# bridge.net
KiCad netlist of a schematic drawn in Altium Designer
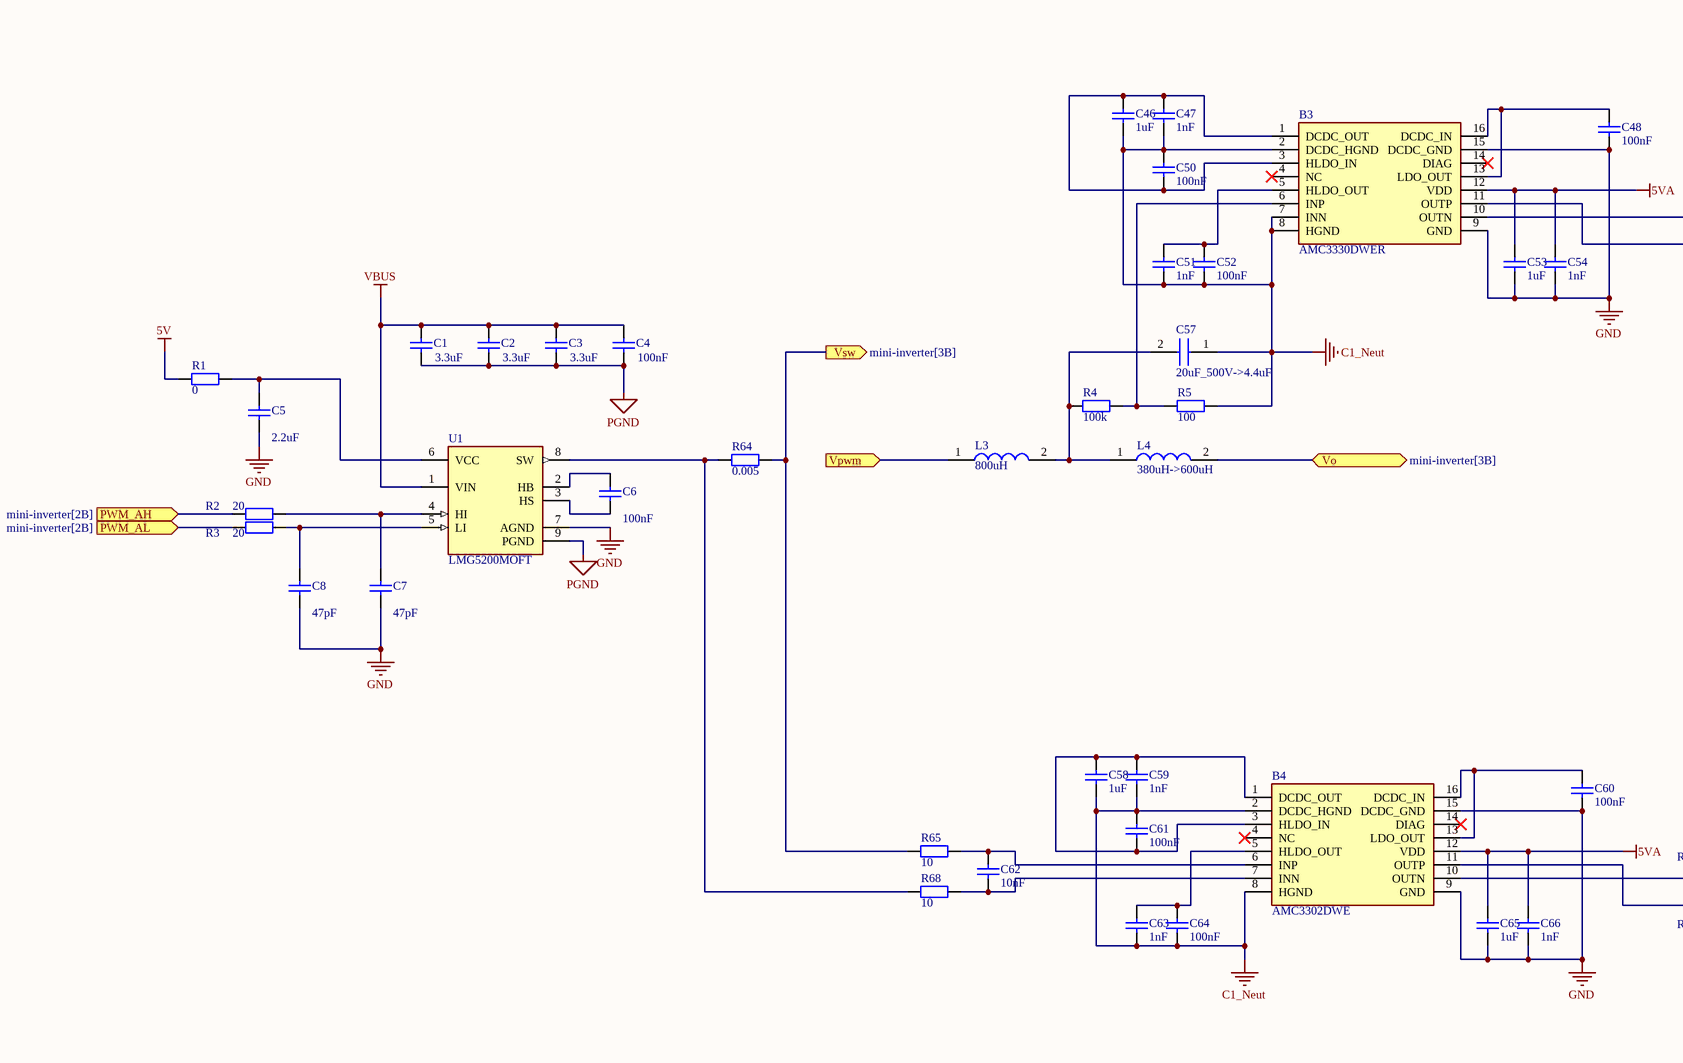
[diagram p0: bridge.SchDoc, left]
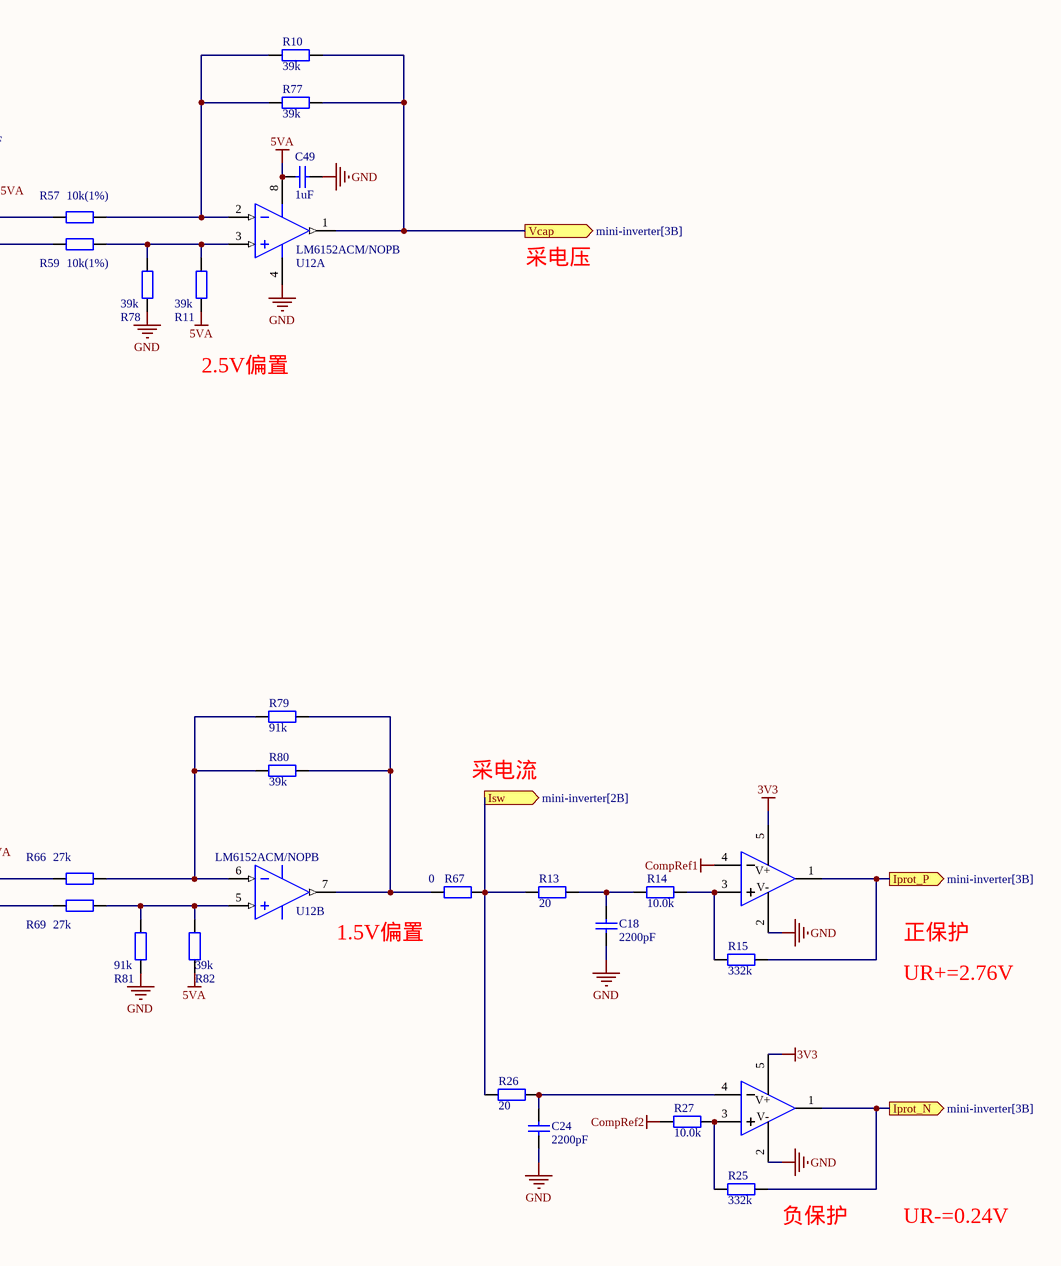
[diagram p1: bridge.SchDoc, right]

(export (version "E")
  (design (tool "Eeschema 10.0.6"))
  (components
    (comp (ref "B3")
      (value "AMC3330DWER")
      (footprint "SOIC127P1030X265-16N")
      (fields (field (name "MOUSER PART NUMBER") "595-AMC3330DWER"))
      (libsource (lib "AMC3330DWER") (part "AMC3330DWER"))
    )
    (comp (ref "B4")
      (value "AMC3302DWE")
      (footprint "SOIC127P1030X265-16N")
      (fields (field (name "MOUSER PART NUMBER") "595-AMC3302DWE"))
      (libsource (lib "AMC3302DWE") (part "AMC3302DWE"))
    )
    (comp (ref "C1")
      (value "3.3uF")
      (footprint "CAPC1608X06N")
      (description "Capacitor")
      (fields (field (name "PUBLISHER") "Altium Limited"))
      (libsource (lib "aaa2") (part "Cap"))
    )
    (comp (ref "C2")
      (value "3.3uF")
      (footprint "CAPC1608X06N")
      (description "Capacitor")
      (fields (field (name "PUBLISHER") "Altium Limited"))
      (libsource (lib "Simscale") (part "Cap"))
    )
    (comp (ref "C3")
      (value "3.3uF")
      (footprint "CAPC1608X06N")
      (description "Capacitor")
      (fields (field (name "PUBLISHER") "Altium Limited"))
      (libsource (lib "Simscale") (part "Cap"))
    )
    (comp (ref "C4")
      (value "100nF")
      (footprint "CAPC1608X06N")
      (description "Capacitor")
      (fields (field (name "PUBLISHER") "Altium Limited"))
      (libsource (lib "Simscale") (part "Cap"))
    )
    (comp (ref "C5")
      (value "2.2uF")
      (footprint "CAPC1608X06N")
      (description "Capacitor")
      (fields (field (name "PUBLISHER") "Altium Limited"))
      (libsource (lib "Simscale") (part "Cap"))
    )
    (comp (ref "C6")
      (value "100nF")
      (footprint "CAPC1608X06N")
      (description "Capacitor")
      (fields (field (name "PUBLISHER") "Altium Limited"))
      (libsource (lib "Simscale") (part "Cap"))
    )
    (comp (ref "C7")
      (value "47pF")
      (footprint "CAPC1608X06N")
      (description "Capacitor")
      (fields (field (name "PUBLISHER") "Altium Limited"))
      (libsource (lib "Simscale") (part "Cap"))
    )
    (comp (ref "C8")
      (value "47pF")
      (footprint "CAPC1608X06N")
      (description "Capacitor")
      (fields (field (name "PUBLISHER") "Altium Limited"))
      (libsource (lib "Simscale") (part "Cap"))
    )
    (comp (ref "C18")
      (value "2200pF")
      (footprint "CAPC1608X06N")
      (description "Capacitor")
      (fields (field (name "PUBLISHER") "Altium Limited"))
      (libsource (lib "Simscale") (part "Cap"))
    )
    (comp (ref "C24")
      (value "2200pF")
      (footprint "CAPC1608X06N")
      (description "Capacitor")
      (fields (field (name "PUBLISHER") "Altium Limited"))
      (libsource (lib "Simscale") (part "Cap"))
    )
    (comp (ref "C46")
      (value "1uF")
      (footprint "CAPC1608X06N")
      (description "Capacitor")
      (fields (field (name "PUBLISHER") "Altium Limited"))
      (libsource (lib "Simscale") (part "Cap"))
    )
    (comp (ref "C47")
      (value "1nF")
      (footprint "CAPC1608X06N")
      (description "Capacitor")
      (fields (field (name "PUBLISHER") "Altium Limited"))
      (libsource (lib "Simscale") (part "Cap"))
    )
    (comp (ref "C48")
      (value "100nF")
      (footprint "CAPC1608X06N")
      (description "Capacitor")
      (fields (field (name "PUBLISHER") "Altium Limited"))
      (libsource (lib "Simscale") (part "Cap"))
    )
    (comp (ref "C49")
      (value "1uF")
      (footprint "CAPC1608X06N")
      (description "Capacitor")
      (fields (field (name "PUBLISHER") "Altium Limited"))
      (libsource (lib "Miscellaneous Devices") (part "Cap"))
    )
    (comp (ref "C50")
      (value "100nF")
      (footprint "CAPC1608X06N")
      (description "Capacitor")
      (fields (field (name "PUBLISHER") "Altium Limited"))
      (libsource (lib "Simscale") (part "Cap"))
    )
    (comp (ref "C51")
      (value "1nF")
      (footprint "CAPC1608X06N")
      (description "Capacitor")
      (fields (field (name "PUBLISHER") "Altium Limited"))
      (libsource (lib "Simscale") (part "Cap"))
    )
    (comp (ref "C52")
      (value "100nF")
      (footprint "CAPC1608X06N")
      (description "Capacitor")
      (fields (field (name "PUBLISHER") "Altium Limited"))
      (libsource (lib "Simscale") (part "Cap"))
    )
    (comp (ref "C53")
      (value "1uF")
      (footprint "CAPC1608X06N")
      (description "Capacitor")
      (fields (field (name "PUBLISHER") "Altium Limited"))
      (libsource (lib "Simscale") (part "Cap"))
    )
    (comp (ref "C54")
      (value "1nF")
      (footprint "CAPC1608X06N")
      (description "Capacitor")
      (fields (field (name "PUBLISHER") "Altium Limited"))
      (libsource (lib "Simscale") (part "Cap"))
    )
    (comp (ref "C57")
      (value "20uF_500V->4.4uF")
      (footprint "Film Capacitor PHE450HF7220JR06L2")
      (description "KEMET PHE450 Metallised Polypropylene Film Capacitor, 180 V ac, 250 V dc, ±5%, 2.2μF, Through Hole")
      (fields (field (name "MANUFACTURER_PART_NUMBER") "PHE450HF7220JR06L2"))
      (libsource (lib "FYP_Components") (part "PHE450HF7220JR06L2"))
    )
    (comp (ref "C58")
      (value "1uF")
      (footprint "CAPC1608X06N")
      (description "Capacitor")
      (fields (field (name "PUBLISHER") "Altium Limited"))
      (libsource (lib "Simscale") (part "Cap"))
    )
    (comp (ref "C59")
      (value "1nF")
      (footprint "CAPC1608X06N")
      (description "Capacitor")
      (fields (field (name "PUBLISHER") "Altium Limited"))
      (libsource (lib "Simscale") (part "Cap"))
    )
    (comp (ref "C60")
      (value "100nF")
      (footprint "CAPC1608X06N")
      (description "Capacitor")
      (fields (field (name "PUBLISHER") "Altium Limited"))
      (libsource (lib "Simscale") (part "Cap"))
    )
    (comp (ref "C61")
      (value "100nF")
      (footprint "CAPC1608X06N")
      (description "Capacitor")
      (fields (field (name "PUBLISHER") "Altium Limited"))
      (libsource (lib "Simscale") (part "Cap"))
    )
    (comp (ref "C62")
      (value "10nF")
      (footprint "CAPC1608X06N")
      (description "Capacitor")
      (fields (field (name "PUBLISHER") "Altium Limited"))
      (libsource (lib "Simscale") (part "Cap"))
    )
    (comp (ref "C63")
      (value "1nF")
      (footprint "CAPC1608X06N")
      (description "Capacitor")
      (fields (field (name "PUBLISHER") "Altium Limited"))
      (libsource (lib "Simscale") (part "Cap"))
    )
    (comp (ref "C64")
      (value "100nF")
      (footprint "CAPC1608X06N")
      (description "Capacitor")
      (fields (field (name "PUBLISHER") "Altium Limited"))
      (libsource (lib "Simscale") (part "Cap"))
    )
    (comp (ref "C65")
      (value "1uF")
      (footprint "CAPC1608X06N")
      (description "Capacitor")
      (fields (field (name "PUBLISHER") "Altium Limited"))
      (libsource (lib "Simscale") (part "Cap"))
    )
    (comp (ref "C66")
      (value "1nF")
      (footprint "CAPC1608X06N")
      (description "Capacitor")
      (fields (field (name "PUBLISHER") "Altium Limited"))
      (libsource (lib "Simscale") (part "Cap"))
    )
    (comp (ref "L3")
      (value "800uH")
      (footprint "4mH Custom")
      (libsource (lib "FYP_Components") (part "4mH Custom Inductor"))
    )
    (comp (ref "L4")
      (value "380uH->600uH")
      (footprint "380uH Custom")
      (libsource (lib "FYP_Components") (part "380uH Custom Inductor"))
    )
    (comp (ref "R1")
      (value "0")
      (footprint "RESC1608X05N")
      (description "贴片电阻")
      (libsource (lib "Simscale") (part "0603 100KΩ (1003) 1%_4"))
    )
    (comp (ref "R2")
      (value "20")
      (footprint "RESC1608X05N")
      (description "贴片电阻")
      (libsource (lib "Simscale") (part "0603 100KΩ (1003) 1%_4"))
    )
    (comp (ref "R3")
      (value "20")
      (footprint "RESC1608X05N")
      (description "贴片电阻")
      (libsource (lib "Simscale") (part "0603 100KΩ (1003) 1%_4"))
    )
    (comp (ref "R4")
      (value "100k")
      (footprint "RESC1608X05N")
      (description "贴片电阻")
      (libsource (lib "") (part "0603 100KΩ (1003) 1%_4_1"))
    )
    (comp (ref "R5")
      (value "100")
      (footprint "RESC1608X05N")
      (description "贴片电阻")
      (libsource (lib "") (part "0603 100KΩ (1003) 1%_4_1"))
    )
    (comp (ref "R10")
      (value "39k")
      (footprint "RESC1608X05N")
      (description "Resistor")
      (fields (field (name "PUBLISHER") "Altium Limited"))
      (libsource (lib "") (part "Res2_1"))
    )
    (comp (ref "R11")
      (value "39k")
      (footprint "RESC1608X05N")
      (description "Resistor")
      (fields (field (name "PUBLISHER") "Altium Limited"))
      (libsource (lib "Miscellaneous Devices") (part "Res2"))
    )
    (comp (ref "R13")
      (value "20")
      (footprint "RESC1608X05N")
      (description "贴片电阻")
      (libsource (lib "Simscale") (part "0603 100KΩ (1003) 1%_4"))
    )
    (comp (ref "R14")
      (value "10.0k")
      (footprint "RESC1608X05N")
      (description "贴片电阻")
      (libsource (lib "Simscale") (part "0603 100KΩ (1003) 1%_4"))
    )
    (comp (ref "R15")
      (value "332k")
      (footprint "RESC1608X05N")
      (description "贴片电阻")
      (libsource (lib "Simscale") (part "0603 100KΩ (1003) 1%_4"))
    )
    (comp (ref "R25")
      (value "332k")
      (footprint "RESC1608X05N")
      (description "贴片电阻")
      (libsource (lib "Simscale") (part "0603 100KΩ (1003) 1%_4"))
    )
    (comp (ref "R26")
      (value "20")
      (footprint "RESC1608X05N")
      (description "贴片电阻")
      (libsource (lib "Simscale") (part "0603 100KΩ (1003) 1%_4"))
    )
    (comp (ref "R27")
      (value "10.0k")
      (footprint "RESC1608X05N")
      (description "贴片电阻")
      (libsource (lib "Simscale") (part "0603 100KΩ (1003) 1%_4"))
    )
    (comp (ref "R57")
      (value "10k(1%)")
      (footprint "RESC1608X05N")
      (description "Resistor")
      (fields (field (name "PUBLISHER") "Altium Limited"))
      (libsource (lib "") (part "Res2_1"))
    )
    (comp (ref "R59")
      (value "10k(1%)")
      (footprint "RESC1608X05N")
      (description "Resistor")
      (fields (field (name "PUBLISHER") "Altium Limited"))
      (libsource (lib "") (part "Res2_2"))
    )
    (comp (ref "R64")
      (value "0.005")
      (footprint "RESC1608X05N")
      (description "贴片电阻")
      (libsource (lib "") (part "0603 100KΩ (1003) 1%_4_1"))
    )
    (comp (ref "R65")
      (value "10")
      (footprint "RESC1608X05N")
      (description "贴片电阻")
      (libsource (lib "") (part "0603 100KΩ (1003) 1%_4_1"))
    )
    (comp (ref "R66")
      (value "27k")
      (footprint "RESC1608X05N")
      (description "Resistor")
      (fields (field (name "PUBLISHER") "Altium Limited"))
      (libsource (lib "") (part "Res2_1"))
    )
    (comp (ref "R67")
      (value "0")
      (footprint "RESC1608X05N")
      (description "Resistor")
      (fields (field (name "PUBLISHER") "Altium Limited"))
      (libsource (lib "") (part "Res2_1"))
    )
    (comp (ref "R68")
      (value "10")
      (footprint "RESC1608X05N")
      (description "贴片电阻")
      (libsource (lib "") (part "0603 100KΩ (1003) 1%_4_1"))
    )
    (comp (ref "R69")
      (value "27k")
      (footprint "RESC1608X05N")
      (description "Resistor")
      (fields (field (name "PUBLISHER") "Altium Limited"))
      (libsource (lib "") (part "Res2_2"))
    )
    (comp (ref "R77")
      (value "39k")
      (footprint "RESC1608X05N")
      (description "Resistor")
      (fields (field (name "PUBLISHER") "Altium Limited"))
      (libsource (lib "") (part "Res2_1"))
    )
    (comp (ref "R78")
      (value "39k")
      (footprint "RESC1608X05N")
      (description "Resistor")
      (fields (field (name "PUBLISHER") "Altium Limited"))
      (libsource (lib "Miscellaneous Devices") (part "Res2"))
    )
    (comp (ref "R79")
      (value "91k")
      (footprint "RESC1608X05N")
      (description "Resistor")
      (fields (field (name "PUBLISHER") "Altium Limited"))
      (libsource (lib "") (part "Res2_2"))
    )
    (comp (ref "R80")
      (value "39k")
      (footprint "RESC1608X05N")
      (description "Resistor")
      (fields (field (name "PUBLISHER") "Altium Limited"))
      (libsource (lib "") (part "Res2_1"))
    )
    (comp (ref "R81")
      (value "91k")
      (footprint "RESC1608X05N")
      (description "Resistor")
      (fields (field (name "PUBLISHER") "Altium Limited"))
      (libsource (lib "Miscellaneous Devices") (part "Res2"))
    )
    (comp (ref "R82")
      (value "39k")
      (footprint "RESC1608X05N")
      (description "Resistor")
      (fields (field (name "PUBLISHER") "Altium Limited"))
      (libsource (lib "Miscellaneous Devices") (part "Res2"))
    )
    (comp (ref "U1")
      (value "LMG5200MOFT")
      (footprint "FP-MOF0009A-MFG")
      (description "None")
      (libsource (lib "Altium Content Vault") (part "e04ca9006c06531c2d1851f29eb7844"))
    )
    (comp (ref "U5")
      (value "TLV3201AIDBVR")
      (footprint "SOT-23-5_L3.0-W1.7-P0.95-LS2.8-BR")
      (fields (field (name "MANUFACTURER") "TI(德州仪器)"))
      (libsource (lib "TLV3201AIDBVR1_TLV3201AIDBVR.schdoc") (part "TLV3201AIDBVR"))
    )
    (comp (ref "U7")
      (value "TLV3201AIDBVR")
      (footprint "SOT-23-5_L3.0-W1.7-P0.95-LS2.8-BR")
      (fields (field (name "MANUFACTURER") "TI(德州仪器)"))
      (libsource (lib "TLV3201AIDBVR1_TLV3201AIDBVR.schdoc") (part "TLV3201AIDBVR"))
    )
    (comp (ref "U12")
      (value "LM6152ACM/NOPB")
      (footprint "D0008A_L")
      (description "Dual and Quad 75 MHz GBW Rail-to-Rail I/O Operational Amplifiers, 8-pin Narrow SOIC, Pb-Free")
      (fields (field (name "MANUFACTURER") "Texas Instruments"))
      (libsource (lib "Simscale") (part "LM6152ACM/NOPB"))
    )
  )
  (nets
    (net (code "1") (name "/Iprot_N") (class "Default")
      (node (ref "R25") (pin "1") (pinfunction "1_1") (pintype "passive"))
      (node (ref "U7") (pin "1") (pinfunction "OUT_1") (pintype "passive"))
    )
    (net (code "2") (name "/Iprot_P") (class "Default")
      (node (ref "R15") (pin "1") (pinfunction "1_1") (pintype "passive"))
      (node (ref "U5") (pin "1") (pinfunction "OUT_1") (pintype "passive"))
    )
    (net (code "3") (name "/Isw") (class "Default")
      (node (ref "R13") (pin "2") (pinfunction "2_2") (pintype "passive"))
      (node (ref "R26") (pin "2") (pinfunction "2_2") (pintype "passive"))
      (node (ref "R67") (pin "1") (pinfunction "1_1") (pintype "passive"))
    )
    (net (code "4") (name "/PWM_AH") (class "Default")
      (node (ref "R2") (pin "2") (pinfunction "2_2") (pintype "passive"))
    )
    (net (code "5") (name "/PWM_AL") (class "Default")
      (node (ref "R3") (pin "2") (pinfunction "2_2") (pintype "passive"))
    )
    (net (code "6") (name "/Vcap") (class "Default")
      (node (ref "R10") (pin "1") (pinfunction "1_1") (pintype "passive"))
      (node (ref "R77") (pin "1") (pinfunction "1_1") (pintype "passive"))
      (node (ref "U12") (pin "1") (pinfunction "OUTA_1") (pintype "output"))
    )
    (net (code "7") (name "/Vo") (class "Default")
      (node (ref "L4") (pin "2") (pinfunction "2_2") (pintype "passive"))
    )
    (net (code "8") (name "/Vpwm") (class "Default")
      (node (ref "L3") (pin "1") (pinfunction "1_1") (pintype "passive"))
    )
    (net (code "9") (name "/Vsw") (class "Default")
      (node (ref "R64") (pin "2") (pinfunction "2_2") (pintype "passive"))
      (node (ref "R65") (pin "1") (pinfunction "1_1") (pintype "passive"))
    )
    (net (code "10") (name "3V3") (class "Default")
      (node (ref "U5") (pin "5") (pinfunction "VCC_5") (pintype "passive"))
      (node (ref "U7") (pin "5") (pinfunction "VCC_5") (pintype "passive"))
    )
    (net (code "11") (name "5V") (class "Default")
      (node (ref "R1") (pin "2") (pinfunction "2_2") (pintype "passive"))
    )
    (net (code "12") (name "5VA") (class "Default")
      (node (ref "B3") (pin "12") (pinfunction "VDD_12") (pintype "passive"))
      (node (ref "B4") (pin "12") (pinfunction "VDD_12") (pintype "passive"))
      (node (ref "C49") (pin "2") (pinfunction "2_2") (pintype "passive"))
      (node (ref "C53") (pin "1") (pinfunction "1_1") (pintype "passive"))
      (node (ref "C54") (pin "1") (pinfunction "1_1") (pintype "passive"))
      (node (ref "C65") (pin "1") (pinfunction "1_1") (pintype "passive"))
      (node (ref "C66") (pin "1") (pinfunction "1_1") (pintype "passive"))
      (node (ref "R11") (pin "1") (pinfunction "1_1") (pintype "passive"))
      (node (ref "R82") (pin "1") (pinfunction "1_1") (pintype "passive"))
      (node (ref "U12") (pin "8") (pinfunction "V+_8") (pintype "power_in"))
    )
    (net (code "13") (name "C1_Neut") (class "Default")
      (node (ref "B3") (pin "2") (pinfunction "DCDC_HGND_2") (pintype "passive"))
      (node (ref "B3") (pin "7") (pinfunction "INN_7") (pintype "passive"))
      (node (ref "B3") (pin "8") (pinfunction "HGND_8") (pintype "passive"))
      (node (ref "B4") (pin "2") (pinfunction "DCDC_HGND_2") (pintype "passive"))
      (node (ref "B4") (pin "8") (pinfunction "HGND_8") (pintype "passive"))
      (node (ref "C46") (pin "2") (pinfunction "2_2") (pintype "passive"))
      (node (ref "C47") (pin "2") (pinfunction "2_2") (pintype "passive"))
      (node (ref "C50") (pin "1") (pinfunction "1_1") (pintype "passive"))
      (node (ref "C51") (pin "2") (pinfunction "2_2") (pintype "passive"))
      (node (ref "C52") (pin "2") (pinfunction "2_2") (pintype "passive"))
      (node (ref "C57") (pin "1") (pinfunction "1_1") (pintype "passive"))
      (node (ref "C58") (pin "2") (pinfunction "2_2") (pintype "passive"))
      (node (ref "C59") (pin "2") (pinfunction "2_2") (pintype "passive"))
      (node (ref "C61") (pin "1") (pinfunction "1_1") (pintype "passive"))
      (node (ref "C63") (pin "2") (pinfunction "2_2") (pintype "passive"))
      (node (ref "C64") (pin "2") (pinfunction "2_2") (pintype "passive"))
      (node (ref "R5") (pin "2") (pinfunction "2_2") (pintype "passive"))
    )
    (net (code "14") (name "CompRef1") (class "Default")
      (node (ref "U5") (pin "4") (pinfunction "IN-_4") (pintype "passive"))
    )
    (net (code "15") (name "CompRef2") (class "Default")
      (node (ref "R27") (pin "2") (pinfunction "2_2") (pintype "passive"))
    )
    (net (code "16") (name "GND") (class "Default")
      (node (ref "B3") (pin "15") (pinfunction "DCDC_GND_15") (pintype "passive"))
      (node (ref "B3") (pin "9") (pinfunction "GND_9") (pintype "passive"))
      (node (ref "B4") (pin "15") (pinfunction "DCDC_GND_15") (pintype "passive"))
      (node (ref "B4") (pin "9") (pinfunction "GND_9") (pintype "passive"))
      (node (ref "C18") (pin "2") (pinfunction "2_2") (pintype "passive"))
      (node (ref "C24") (pin "2") (pinfunction "2_2") (pintype "passive"))
      (node (ref "C48") (pin "2") (pinfunction "2_2") (pintype "passive"))
      (node (ref "C49") (pin "1") (pinfunction "1_1") (pintype "passive"))
      (node (ref "C5") (pin "1") (pinfunction "1_1") (pintype "passive"))
      (node (ref "C53") (pin "2") (pinfunction "2_2") (pintype "passive"))
      (node (ref "C54") (pin "2") (pinfunction "2_2") (pintype "passive"))
      (node (ref "C60") (pin "2") (pinfunction "2_2") (pintype "passive"))
      (node (ref "C65") (pin "2") (pinfunction "2_2") (pintype "passive"))
      (node (ref "C66") (pin "2") (pinfunction "2_2") (pintype "passive"))
      (node (ref "C7") (pin "2") (pinfunction "2_2") (pintype "passive"))
      (node (ref "C8") (pin "2") (pinfunction "2_2") (pintype "passive"))
      (node (ref "R78") (pin "1") (pinfunction "1_1") (pintype "passive"))
      (node (ref "R81") (pin "1") (pinfunction "1_1") (pintype "passive"))
      (node (ref "U1") (pin "7") (pinfunction "AGND_7") (pintype "power_in"))
      (node (ref "U12") (pin "4") (pinfunction "V-_4") (pintype "power_in"))
      (node (ref "U5") (pin "2") (pinfunction "GND_2") (pintype "passive"))
      (node (ref "U7") (pin "2") (pinfunction "GND_2") (pintype "passive"))
    )
    (net (code "17") (name "Net-(B3-DCDC_IN)") (class "Default")
      (node (ref "B3") (pin "13") (pinfunction "LDO_OUT_13") (pintype "passive"))
      (node (ref "B3") (pin "16") (pinfunction "DCDC_IN_16") (pintype "passive"))
      (node (ref "C48") (pin "1") (pinfunction "1_1") (pintype "passive"))
    )
    (net (code "18") (name "Net-(B3-DCDC_OUT)") (class "Default")
      (node (ref "B3") (pin "1") (pinfunction "DCDC_OUT_1") (pintype "passive"))
      (node (ref "B3") (pin "3") (pinfunction "HLDO_IN_3") (pintype "passive"))
      (node (ref "C46") (pin "1") (pinfunction "1_1") (pintype "passive"))
      (node (ref "C47") (pin "1") (pinfunction "1_1") (pintype "passive"))
      (node (ref "C50") (pin "2") (pinfunction "2_2") (pintype "passive"))
    )
    (net (code "19") (name "Net-(B3-HLDO_OUT)") (class "Default")
      (node (ref "B3") (pin "5") (pinfunction "HLDO_OUT_5") (pintype "passive"))
      (node (ref "C51") (pin "1") (pinfunction "1_1") (pintype "passive"))
      (node (ref "C52") (pin "1") (pinfunction "1_1") (pintype "passive"))
    )
    (net (code "20") (name "Net-(B3-INP)") (class "Default")
      (node (ref "B3") (pin "6") (pinfunction "INP_6") (pintype "passive"))
      (node (ref "R4") (pin "2") (pinfunction "2_2") (pintype "passive"))
      (node (ref "R5") (pin "1") (pinfunction "1_1") (pintype "passive"))
    )
    (net (code "21") (name "Net-(B3-OUTN)") (class "Default")
      (node (ref "B3") (pin "10") (pinfunction "OUTN_10") (pintype "passive"))
      (node (ref "R57") (pin "2") (pinfunction "2_2") (pintype "passive"))
    )
    (net (code "22") (name "Net-(B3-OUTP)") (class "Default")
      (node (ref "B3") (pin "11") (pinfunction "OUTP_11") (pintype "passive"))
      (node (ref "R59") (pin "1") (pinfunction "1_1") (pintype "passive"))
    )
    (net (code "23") (name "Net-(B4-DCDC_IN)") (class "Default")
      (node (ref "B4") (pin "13") (pinfunction "LDO_OUT_13") (pintype "passive"))
      (node (ref "B4") (pin "16") (pinfunction "DCDC_IN_16") (pintype "passive"))
      (node (ref "C60") (pin "1") (pinfunction "1_1") (pintype "passive"))
    )
    (net (code "24") (name "Net-(B4-DCDC_OUT)") (class "Default")
      (node (ref "B4") (pin "1") (pinfunction "DCDC_OUT_1") (pintype "passive"))
      (node (ref "B4") (pin "3") (pinfunction "HLDO_IN_3") (pintype "passive"))
      (node (ref "C58") (pin "1") (pinfunction "1_1") (pintype "passive"))
      (node (ref "C59") (pin "1") (pinfunction "1_1") (pintype "passive"))
      (node (ref "C61") (pin "2") (pinfunction "2_2") (pintype "passive"))
    )
    (net (code "25") (name "Net-(B4-HLDO_OUT)") (class "Default")
      (node (ref "B4") (pin "5") (pinfunction "HLDO_OUT_5") (pintype "passive"))
      (node (ref "C63") (pin "1") (pinfunction "1_1") (pintype "passive"))
      (node (ref "C64") (pin "1") (pinfunction "1_1") (pintype "passive"))
    )
    (net (code "26") (name "Net-(B4-INN)") (class "Default")
      (node (ref "B4") (pin "7") (pinfunction "INN_7") (pintype "passive"))
      (node (ref "C62") (pin "2") (pinfunction "2_2") (pintype "passive"))
      (node (ref "R68") (pin "2") (pinfunction "2_2") (pintype "passive"))
    )
    (net (code "27") (name "Net-(B4-INP)") (class "Default")
      (node (ref "B4") (pin "6") (pinfunction "INP_6") (pintype "passive"))
      (node (ref "C62") (pin "1") (pinfunction "1_1") (pintype "passive"))
      (node (ref "R65") (pin "2") (pinfunction "2_2") (pintype "passive"))
    )
    (net (code "28") (name "Net-(B4-OUTN)") (class "Default")
      (node (ref "B4") (pin "10") (pinfunction "OUTN_10") (pintype "passive"))
      (node (ref "R66") (pin "2") (pinfunction "2_2") (pintype "passive"))
    )
    (net (code "29") (name "Net-(B4-OUTP)") (class "Default")
      (node (ref "B4") (pin "11") (pinfunction "OUTP_11") (pintype "passive"))
      (node (ref "R69") (pin "1") (pinfunction "1_1") (pintype "passive"))
    )
    (net (code "30") (name "Net-(C18-Pad1)") (class "Default")
      (node (ref "C18") (pin "1") (pinfunction "1_1") (pintype "passive"))
      (node (ref "R13") (pin "1") (pinfunction "1_1") (pintype "passive"))
      (node (ref "R14") (pin "2") (pinfunction "2_2") (pintype "passive"))
    )
    (net (code "31") (name "Net-(C57-Pad2)") (class "Default")
      (node (ref "C57") (pin "2") (pinfunction "2_2") (pintype "passive"))
      (node (ref "L3") (pin "2") (pinfunction "2_2") (pintype "passive"))
      (node (ref "L4") (pin "1") (pinfunction "1_1") (pintype "passive"))
      (node (ref "R4") (pin "1") (pinfunction "1_1") (pintype "passive"))
    )
    (net (code "32") (name "Net-(U1-HB)") (class "Default")
      (node (ref "C6") (pin "1") (pinfunction "1_1") (pintype "passive"))
      (node (ref "U1") (pin "2") (pinfunction "HB_2") (pintype "passive"))
    )
    (net (code "33") (name "Net-(U1-HI)") (class "Default")
      (node (ref "C7") (pin "1") (pinfunction "1_1") (pintype "passive"))
      (node (ref "R2") (pin "1") (pinfunction "1_1") (pintype "passive"))
      (node (ref "U1") (pin "4") (pinfunction "HI_4") (pintype "input"))
    )
    (net (code "34") (name "Net-(U1-HS)") (class "Default")
      (node (ref "C6") (pin "2") (pinfunction "2_2") (pintype "passive"))
      (node (ref "U1") (pin "3") (pinfunction "HS_3") (pintype "passive"))
    )
    (net (code "35") (name "Net-(U1-LI)") (class "Default")
      (node (ref "C8") (pin "1") (pinfunction "1_1") (pintype "passive"))
      (node (ref "R3") (pin "1") (pinfunction "1_1") (pintype "passive"))
      (node (ref "U1") (pin "5") (pinfunction "LI_5") (pintype "input"))
    )
    (net (code "36") (name "Net-(U1-SW)") (class "Default")
      (node (ref "R64") (pin "1") (pinfunction "1_1") (pintype "passive"))
      (node (ref "R68") (pin "1") (pinfunction "1_1") (pintype "passive"))
      (node (ref "U1") (pin "8") (pinfunction "SW_8") (pintype "output"))
    )
    (net (code "37") (name "Net-(U1-VCC)") (class "Default")
      (node (ref "C5") (pin "2") (pinfunction "2_2") (pintype "passive"))
      (node (ref "R1") (pin "1") (pinfunction "1_1") (pintype "passive"))
      (node (ref "U1") (pin "6") (pinfunction "VCC_6") (pintype "power_in"))
    )
    (net (code "38") (name "Net-(U5-IN+)") (class "Default")
      (node (ref "R14") (pin "1") (pinfunction "1_1") (pintype "passive"))
      (node (ref "R15") (pin "2") (pinfunction "2_2") (pintype "passive"))
      (node (ref "U5") (pin "3") (pinfunction "IN+_3") (pintype "passive"))
    )
    (net (code "39") (name "Net-(U7-IN+)") (class "Default")
      (node (ref "R25") (pin "2") (pinfunction "2_2") (pintype "passive"))
      (node (ref "R27") (pin "1") (pinfunction "1_1") (pintype "passive"))
      (node (ref "U7") (pin "3") (pinfunction "IN+_3") (pintype "passive"))
    )
    (net (code "40") (name "Net-(U7-IN-)") (class "Default")
      (node (ref "C24") (pin "1") (pinfunction "1_1") (pintype "passive"))
      (node (ref "R26") (pin "1") (pinfunction "1_1") (pintype "passive"))
      (node (ref "U7") (pin "4") (pinfunction "IN-_4") (pintype "passive"))
    )
    (net (code "41") (name "Net-(U12A-INA+)") (class "Default")
      (node (ref "R11") (pin "2") (pinfunction "2_2") (pintype "passive"))
      (node (ref "R59") (pin "2") (pinfunction "2_2") (pintype "passive"))
      (node (ref "R78") (pin "2") (pinfunction "2_2") (pintype "passive"))
      (node (ref "U12") (pin "3") (pinfunction "INA+_3") (pintype "input"))
    )
    (net (code "42") (name "Net-(U12A-INA-)") (class "Default")
      (node (ref "R10") (pin "2") (pinfunction "2_2") (pintype "passive"))
      (node (ref "R57") (pin "1") (pinfunction "1_1") (pintype "passive"))
      (node (ref "R77") (pin "2") (pinfunction "2_2") (pintype "passive"))
      (node (ref "U12") (pin "2") (pinfunction "INA-_2") (pintype "input"))
    )
    (net (code "43") (name "Net-(U12B-INB+)") (class "Default")
      (node (ref "R69") (pin "2") (pinfunction "2_2") (pintype "passive"))
      (node (ref "R81") (pin "2") (pinfunction "2_2") (pintype "passive"))
      (node (ref "R82") (pin "2") (pinfunction "2_2") (pintype "passive"))
      (node (ref "U12") (pin "5") (pinfunction "INB+_5") (pintype "input"))
    )
    (net (code "44") (name "Net-(U12B-INB-)") (class "Default")
      (node (ref "R66") (pin "1") (pinfunction "1_1") (pintype "passive"))
      (node (ref "R79") (pin "1") (pinfunction "1_1") (pintype "passive"))
      (node (ref "R80") (pin "2") (pinfunction "2_2") (pintype "passive"))
      (node (ref "U12") (pin "6") (pinfunction "INB-_6") (pintype "input"))
    )
    (net (code "45") (name "Net-(U12B-OUTB)") (class "Default")
      (node (ref "R67") (pin "2") (pinfunction "2_2") (pintype "passive"))
      (node (ref "R79") (pin "2") (pinfunction "2_2") (pintype "passive"))
      (node (ref "R80") (pin "1") (pinfunction "1_1") (pintype "passive"))
      (node (ref "U12") (pin "7") (pinfunction "OUTB_7") (pintype "output"))
    )
    (net (code "46") (name "PGND") (class "Default")
      (node (ref "C1") (pin "1") (pinfunction "1_1") (pintype "passive"))
      (node (ref "C2") (pin "1") (pinfunction "1_1") (pintype "passive"))
      (node (ref "C3") (pin "1") (pinfunction "1_1") (pintype "passive"))
      (node (ref "C4") (pin "2") (pinfunction "2_2") (pintype "passive"))
      (node (ref "U1") (pin "9") (pinfunction "PGND_9") (pintype "power_in"))
    )
    (net (code "47") (name "VBUS") (class "Default")
      (node (ref "C1") (pin "2") (pinfunction "2_2") (pintype "passive"))
      (node (ref "C2") (pin "2") (pinfunction "2_2") (pintype "passive"))
      (node (ref "C3") (pin "2") (pinfunction "2_2") (pintype "passive"))
      (node (ref "C4") (pin "1") (pinfunction "1_1") (pintype "passive"))
      (node (ref "U1") (pin "1") (pinfunction "VIN_1") (pintype "power_in"))
    )
    (net (code "48") (name "unconnected-(B3-DIAG-Pad14)") (class "Default")
      (node (ref "B3") (pin "14") (pinfunction "DIAG_14") (pintype "passive+no_connect"))
    )
    (net (code "49") (name "unconnected-(B3-NC-Pad4)") (class "Default")
      (node (ref "B3") (pin "4") (pinfunction "NC_4") (pintype "passive+no_connect"))
    )
    (net (code "50") (name "unconnected-(B4-DIAG-Pad14)") (class "Default")
      (node (ref "B4") (pin "14") (pinfunction "DIAG_14") (pintype "passive+no_connect"))
    )
    (net (code "51") (name "unconnected-(B4-NC-Pad4)") (class "Default")
      (node (ref "B4") (pin "4") (pinfunction "NC_4") (pintype "passive+no_connect"))
    )
  )
)
